# Sheet1.net
KiCad netlist of a schematic drawn in Altium Designer
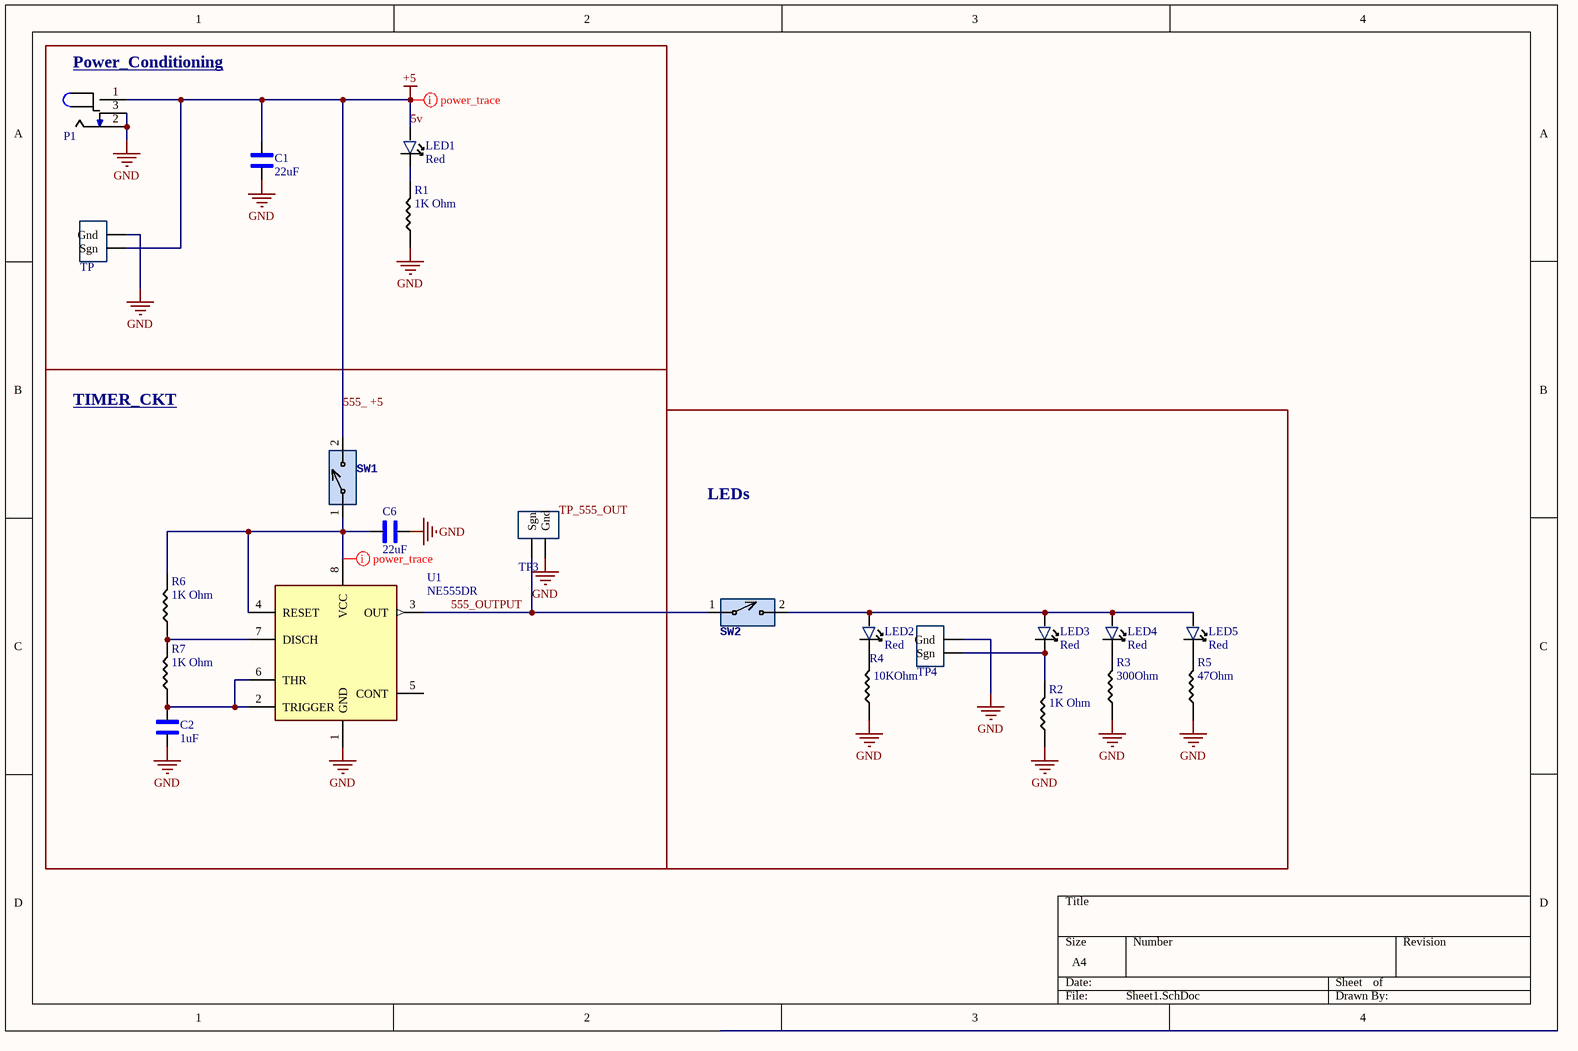
[diagram p0: Sheet1.SchDoc]

(export (version "E")
  (design (tool "Eeschema 10.0.6"))
  (components
    (comp (ref "C1")
      (value "22uF")
      (footprint "1206_Passive_Capacitor")
      (description "MULTILAYER CERAMIC CAPACITORS MLCC - SMD/SMT 1UF 50V 1206 ROHS")
      (fields (field (name "DIGIKEY PART") "399-8150-1-ND") (field (name "MFR PART #") "CL31B105KBHNNNE"))
      (libsource (lib "ECEN5730Lib_JLC_2021_07") (part "C_1uF_1206"))
    )
    (comp (ref "C2")
      (value "1uF")
      (footprint "1206_Passive_Capacitor")
      (description "MULTILAYER CERAMIC CAPACITORS MLCC - SMD/SMT 1UF 50V 1206 ROHS")
      (fields (field (name "DIGIKEY PART") "399-8150-1-ND") (field (name "MFR PART #") "CL31B105KBHNNNE"))
      (libsource (lib "ECEN5730Lib_JLC_2021_07") (part "C_1uF_1206"))
    )
    (comp (ref "C6")
      (value "22uF")
      (footprint "0402_Passive_Capacitor")
      (description "MULTILAYER CERAMIC CAPACITORS MLCC - SMD/SMT 22PF 50V 0402 ROHS")
      (fields (field (name "MFR PART #") "0402CG220J500NT") (field (name "LCSC PART#") "C1555"))
      (libsource (lib "ECEN5730Lib_JLC_2021_07") (part "C_22pF_0402"))
    )
    (comp (ref "LED1")
      (value "Red")
      (footprint "LED_0603")
      (description "LIGHT EMITTING DIODES (LED) RED 520~625NM 90~100MCD@20MA TOP VIEW 0603 ROHS")
      (fields (field (name "MFR PART #") "KT-0603R") (field (name "LCSC PART#") "C2286"))
      (libsource (lib "ECEN5730Lib_JLC_2021_07") (part "LED_RED_0603"))
    )
    (comp (ref "LED2")
      (value "Red")
      (footprint "LED_0603")
      (description "LIGHT EMITTING DIODES (LED) RED 520~625NM 90~100MCD@20MA TOP VIEW 0603 ROHS")
      (fields (field (name "MFR PART #") "KT-0603R") (field (name "LCSC PART#") "C2286"))
      (libsource (lib "ECEN5730Lib_JLC_2021_07") (part "LED_RED_0603"))
    )
    (comp (ref "LED3")
      (value "Red")
      (footprint "LED_0603")
      (description "LIGHT EMITTING DIODES (LED) RED 520~625NM 90~100MCD@20MA TOP VIEW 0603 ROHS")
      (fields (field (name "MFR PART #") "KT-0603R") (field (name "LCSC PART#") "C2286"))
      (libsource (lib "ECEN5730Lib_JLC_2021_07") (part "LED_RED_0603"))
    )
    (comp (ref "LED4")
      (value "Red")
      (footprint "LED_0603")
      (description "LIGHT EMITTING DIODES (LED) RED 520~625NM 90~100MCD@20MA TOP VIEW 0603 ROHS")
      (fields (field (name "MFR PART #") "KT-0603R") (field (name "LCSC PART#") "C2286"))
      (libsource (lib "ECEN5730Lib_JLC_2021_07") (part "LED_RED_0603"))
    )
    (comp (ref "LED5")
      (value "Red")
      (footprint "LED_0603")
      (description "LIGHT EMITTING DIODES (LED) RED 520~625NM 90~100MCD@20MA TOP VIEW 0603 ROHS")
      (fields (field (name "MFR PART #") "KT-0603R") (field (name "LCSC PART#") "C2286"))
      (libsource (lib "ECEN5730Lib_JLC_2021_07") (part "LED_RED_0603"))
    )
    (comp (ref "P1")
      (value "Power Jack")
      (footprint "Power_Jack")
      (description "Power Barrel Connector Jack 2.10mm ID (0.083\"), 5.50mm OD (0.217\") Through Hole, Right Angle")
      (fields (field (name "DIGIKEY PART") "CP-102A-ND") (field (name "LCSC PART#") "C136744"))
      (libsource (lib "ECEN5730Lib_JLC_2021_07") (part "P_Power Jack"))
    )
    (comp (ref "R1")
      (value "1K Ohm")
      (footprint "1206_Passive_Resitor")
      (description "CHIP RESISTOR - SURFACE MOUNT 1KOHMS ±1% 1/4W 1206 ROHS")
      (fields (field (name "DIGIKEY PART") "RNCP1206FTD1K00CT-ND") (field (name "LCSC PART#") "C4410"))
      (libsource (lib "ECEN5730Lib_JLC_2021_07") (part "R_1K_1206"))
    )
    (comp (ref "R2")
      (value "1K Ohm")
      (footprint "1206_Passive_Resitor")
      (description "CHIP RESISTOR - SURFACE MOUNT 1KOHMS ±1% 1/4W 1206 ROHS")
      (fields (field (name "DIGIKEY PART") "RNCP1206FTD1K00CT-ND") (field (name "LCSC PART#") "C4410"))
      (libsource (lib "ECEN5730Lib_JLC_2021_07") (part "R_1K_1206"))
    )
    (comp (ref "R3")
      (value "300Ohm")
      (footprint "1206_Passive_Resitor")
      (description "CHIP RESISTOR - SURFACE MOUNT 300OHMS ±1% 1/4W 1206 ROHS")
      (fields (field (name "MFR PART #") "1206W4F3000T5E") (field (name "LCSC PART#") "C17887"))
      (libsource (lib "ECEN5730Lib_JLC_2021_07") (part "R_300Ohm_1206"))
    )
    (comp (ref "R4")
      (value "10KOhm")
      (footprint "1206_Passive_Resitor")
      (description "10 kOhms ±5% 0.25W, 1/4W Chip Resistor 1206 (3216 Metric) Automotive AEC-Q200 Thick Film")
      (fields (field (name "DIGIKEY PART") "RMCF1206JT300RCT-ND") (field (name "LCSC PART#") "C17902"))
      (libsource (lib "ECEN5730Lib_JLC_2021_07") (part "R_10KOhm_1206"))
    )
    (comp (ref "R5")
      (value "47Ohm")
      (footprint "1206_Passive_Resitor")
      (description "47Ω ±5% 0.25W ±200ppm/℃ 1206 Chip Resistor - Surface Mount RoHS")
      (fields (field (name "MFR PART #") "1206W4J0470T5E") (field (name "LCSC PART#") "C25384"))
      (libsource (lib "ECEN5730Lib_JLC_2021_07") (part "R_47Ohm_1206"))
    )
    (comp (ref "R6")
      (value "1K Ohm")
      (footprint "1206_Passive_Resitor")
      (description "CHIP RESISTOR - SURFACE MOUNT 1KOHMS ±1% 1/4W 1206 ROHS")
      (fields (field (name "DIGIKEY PART") "RNCP1206FTD1K00CT-ND") (field (name "LCSC PART#") "C4410"))
      (libsource (lib "ECEN5730Lib_JLC_2021_07") (part "R_1K_1206"))
    )
    (comp (ref "R7")
      (value "1K Ohm")
      (footprint "1206_Passive_Resitor")
      (description "CHIP RESISTOR - SURFACE MOUNT 1KOHMS ±1% 1/4W 1206 ROHS")
      (fields (field (name "DIGIKEY PART") "RNCP1206FTD1K00CT-ND") (field (name "LCSC PART#") "C4410"))
      (libsource (lib "ECEN5730Lib_JLC_2021_07") (part "R_1K_1206"))
    )
    (comp (ref "SW1")
      (value "on_off_switch")
      (footprint "2Pin-Header-Conn")
      (description "2Pin Header")
      (fields (field (name "LCSC PART#") "C124375"))
      (libsource (lib "ECEN5730Lib_JLC_2021_07") (part "SW_2Pin_100mil_Switch"))
    )
    (comp (ref "SW2")
      (value "SW_2Pin_100mil_Switch")
      (footprint "2Pin-Header-Conn")
      (description "2Pin Header")
      (fields (field (name "LCSC PART#") "C124375"))
      (libsource (lib "") (part "SW_2Pin_100mil_Switch_1"))
    )
    (comp (ref "TP")
      (value "TP_5V")
      (footprint "TP10x_Probe")
      (description "Test Point 300 mil centers")
      (libsource (lib "ECEN5730Lib_Manual_2021_07") (part "TP_10x_Probe"))
    )
    (comp (ref "TP3")
      (value "TP_555_OUTPUT")
      (footprint "TP10x_Probe")
      (description "Test Point 300 mil centers")
      (libsource (lib "") (part "TP_10x_Probe_1"))
    )
    (comp (ref "TP4")
      (value "10x Probe TP")
      (footprint "TP10x_Probe")
      (description "Test Point 300 mil centers")
      (libsource (lib "ECEN5730Lib_Manual_2021_07") (part "TP_10x_Probe"))
    )
    (comp (ref "U1")
      (value "NE555DR")
      (footprint "TS555IDTTR")
      (description "555 Timer SOIC-8_150MIL ROHS 150ns Rise Time")
      (fields (field (name "LCSC PART#") "C7593"))
      (libsource (lib "ECEN5730Lib_JLC_2021_07") (part "U_555_Slow"))
    )
  )
  (nets
    (net (code "1") (name "+5") (class "Default")
      (node (ref "C1") (pin "2") (pinfunction "2_2") (pintype "passive"))
      (node (ref "LED1") (pin "1") (pinfunction "1_1") (pintype "passive"))
      (node (ref "P1") (pin "1") (pinfunction "1_1") (pintype "power_in"))
      (node (ref "SW1") (pin "2") (pinfunction "2_2") (pintype "passive"))
      (node (ref "TP") (pin "1") (pinfunction "Sgn_1") (pintype "passive"))
    )
    (net (code "2") (name "/555_OUTPUT") (class "Default")
      (node (ref "SW2") (pin "1") (pinfunction "1_1") (pintype "passive"))
      (node (ref "TP3") (pin "1") (pinfunction "Sgn_1") (pintype "passive"))
      (node (ref "U1") (pin "3") (pinfunction "OUT_3") (pintype "output"))
    )
    (net (code "4") (name "GND") (class "Default")
      (node (ref "C1") (pin "1") (pinfunction "1_1") (pintype "passive"))
      (node (ref "C2") (pin "1") (pinfunction "1_1") (pintype "passive"))
      (node (ref "C6") (pin "2") (pinfunction "2_2") (pintype "passive"))
      (node (ref "P1") (pin "2") (pinfunction "2_2") (pintype "power_in"))
      (node (ref "P1") (pin "3") (pinfunction "3_3") (pintype "power_in"))
      (node (ref "R1") (pin "1") (pinfunction "1_1") (pintype "passive"))
      (node (ref "R2") (pin "1") (pinfunction "1_1") (pintype "passive"))
      (node (ref "R3") (pin "1") (pinfunction "1_1") (pintype "passive"))
      (node (ref "R4") (pin "1") (pinfunction "1_1") (pintype "passive"))
      (node (ref "R5") (pin "1") (pinfunction "1_1") (pintype "passive"))
      (node (ref "TP") (pin "2") (pinfunction "Gnd_2") (pintype "passive"))
      (node (ref "TP3") (pin "2") (pinfunction "Gnd_2") (pintype "passive"))
      (node (ref "TP4") (pin "2") (pinfunction "Gnd_2") (pintype "passive"))
      (node (ref "U1") (pin "1") (pinfunction "GND_1") (pintype "power_in"))
    )
    (net (code "5") (name "Net-(LED1-Pad2)") (class "Default")
      (node (ref "LED1") (pin "2") (pinfunction "2_2") (pintype "passive"))
      (node (ref "R1") (pin "2") (pinfunction "2_2") (pintype "passive"))
    )
    (net (code "6") (name "Net-(LED2-Pad1)") (class "Default")
      (node (ref "LED2") (pin "1") (pinfunction "1_1") (pintype "passive"))
      (node (ref "LED3") (pin "1") (pinfunction "1_1") (pintype "passive"))
      (node (ref "LED4") (pin "1") (pinfunction "1_1") (pintype "passive"))
      (node (ref "LED5") (pin "1") (pinfunction "1_1") (pintype "passive"))
      (node (ref "SW2") (pin "2") (pinfunction "2_2") (pintype "passive"))
    )
    (net (code "7") (name "Net-(LED2-Pad2)") (class "Default")
      (node (ref "LED2") (pin "2") (pinfunction "2_2") (pintype "passive"))
      (node (ref "R4") (pin "2") (pinfunction "2_2") (pintype "passive"))
    )
    (net (code "8") (name "Net-(LED4-Pad2)") (class "Default")
      (node (ref "LED4") (pin "2") (pinfunction "2_2") (pintype "passive"))
      (node (ref "R3") (pin "2") (pinfunction "2_2") (pintype "passive"))
    )
    (net (code "9") (name "Net-(LED5-Pad2)") (class "Default")
      (node (ref "LED5") (pin "2") (pinfunction "2_2") (pintype "passive"))
      (node (ref "R5") (pin "2") (pinfunction "2_2") (pintype "passive"))
    )
    (net (code "10") (name "Net-(TP4-Sgn)") (class "Default")
      (node (ref "LED3") (pin "2") (pinfunction "2_2") (pintype "passive"))
      (node (ref "R2") (pin "2") (pinfunction "2_2") (pintype "passive"))
      (node (ref "TP4") (pin "1") (pinfunction "Sgn_1") (pintype "passive"))
    )
    (net (code "11") (name "Net-(U1-DISCH)") (class "Default")
      (node (ref "R6") (pin "1") (pinfunction "1_1") (pintype "passive"))
      (node (ref "R7") (pin "2") (pinfunction "2_2") (pintype "passive"))
      (node (ref "U1") (pin "7") (pinfunction "DISCH_7") (pintype "passive"))
    )
    (net (code "12") (name "Net-(U1-RESET)") (class "Default")
      (node (ref "C6") (pin "1") (pinfunction "1_1") (pintype "passive"))
      (node (ref "R6") (pin "2") (pinfunction "2_2") (pintype "passive"))
      (node (ref "SW1") (pin "1") (pinfunction "1_1") (pintype "passive"))
      (node (ref "U1") (pin "4") (pinfunction "RESET_4") (pintype "passive"))
      (node (ref "U1") (pin "8") (pinfunction "VCC_8") (pintype "power_in"))
    )
    (net (code "13") (name "Net-(U1-THR)") (class "Default")
      (node (ref "C2") (pin "2") (pinfunction "2_2") (pintype "passive"))
      (node (ref "R7") (pin "1") (pinfunction "1_1") (pintype "passive"))
      (node (ref "U1") (pin "2") (pinfunction "TRIGGER_2") (pintype "passive"))
      (node (ref "U1") (pin "6") (pinfunction "THR_6") (pintype "passive"))
    )
    (net (code "14") (name "unconnected-(U1-CONT-Pad5)") (class "Default")
      (node (ref "U1") (pin "5") (pinfunction "CONT_5") (pintype "passive"))
    )
  )
)
